# NewPower.net
KiCad netlist of a schematic drawn in Altium Designer
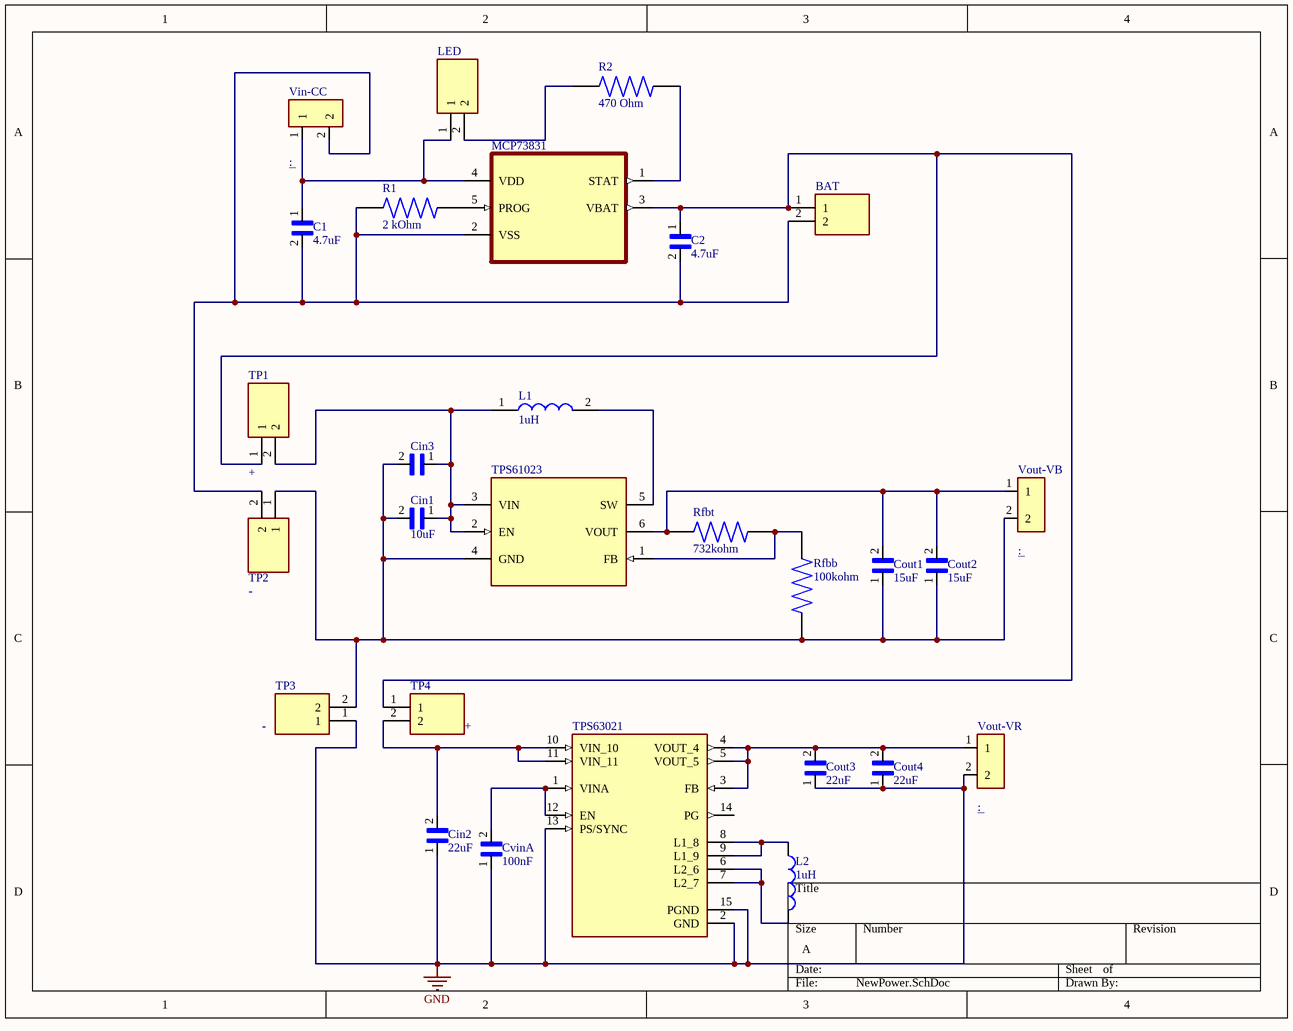
[diagram p0: NewPower.SchDoc]

(export (version "E")
  (design (tool "Eeschema 10.0.6"))
  (components
    (comp (ref "BAT")
      (value "~")
      (footprint "JST_S2B-PH-K-S(LF)(SN)")
      (description "Connector Header Through Hole, Right Angle 2 position")
      (fields (field (name "MP") "S2B-PH-K-S(LF)(SN)") (field (name "MF") "JST Sales America Inc."))
      (libsource (lib "S2B-PH-K-S_LF__SN_") (part "S2B-PH-K-S(LF)(SN)"))
    )
    (comp (ref "C1")
      (value "4.7uF")
      (footprint "CAPC1005X55N")
      (description "4.7ÂµF Â±20% 10V Ceramic Capacitor X5R 0402 (1005 Metric)")
      (fields (field (name "MP") "CL05A475MP5NRNC") (field (name "MF") "Samsung Electro-Mechanics"))
      (libsource (lib "CL05A475MP5NRNC") (part "CL05A475MP5NRNC"))
    )
    (comp (ref "C2")
      (value "4.7uF")
      (footprint "CAPC1005X55N")
      (description "4.7ÂµF Â±20% 10V Ceramic Capacitor X5R 0402 (1005 Metric)")
      (fields (field (name "MP") "CL05A475MP5NRNC") (field (name "MF") "Samsung Electro-Mechanics"))
      (libsource (lib "CL05A475MP5NRNC") (part "CL05A475MP5NRNC"))
    )
    (comp (ref "Cin1")
      (value "10uF")
      (footprint "CAPC2012X88N")
      (description "10渭F 卤 10% Capacitor de cer芒mica 10V X5R 0805 _2012 M茅trico_")
      (fields (field (name "MF") "KEMET") (field (name "DIGI-KEY_PART_NUMBER") "399-4925-1-ND"))
      (libsource (lib "C0805C106K8PACTU") (part "C0805C106K8PACTU"))
    )
    (comp (ref "Cin2")
      (value "22uF")
      (footprint "CAPC1608X100N")
      (description "SMD Capacitor X5R_EIA_ with Capacitance: 22uF Tol. 20%. Rated Voltage: 6.3Vdc")
      (fields (field (name "MF") "Murata") (field (name "DIGI-KEY_PART_NUMBER") "490-7611-1-ND"))
      (libsource (lib "GRM188R60J226MEA0D") (part "GRM188R60J226MEA0D"))
    )
    (comp (ref "Cin3")
      (value "~")
      (footprint "CAPC2012X88N")
      (description "10渭F 卤 10% Capacitor de cer芒mica 10V X5R 0805 _2012 M茅trico_")
      (fields (field (name "MF") "KEMET") (field (name "DIGI-KEY_PART_NUMBER") "399-4925-1-ND"))
      (libsource (lib "C0805C106K8PACTU") (part "C0805C106K8PACTU"))
    )
    (comp (ref "Cout1")
      (value "15uF")
      (footprint "CAPC2012X145N")
      (description "15ÂµF Â±20% 35V Ceramic Capacitor X5R 0805 (2012 Metric)")
      (fields (field (name "MF") "TDK") (field (name "MP") "C2012X5R1V156M125AC"))
      (libsource (lib "C2012X5R1V156M125AC") (part "C2012X5R1V156M125AC"))
    )
    (comp (ref "Cout2")
      (value "15uF")
      (footprint "CAPC2012X145N")
      (description "15ÂµF Â±20% 35V Ceramic Capacitor X5R 0805 (2012 Metric)")
      (fields (field (name "MF") "TDK") (field (name "MP") "C2012X5R1V156M125AC"))
      (libsource (lib "C2012X5R1V156M125AC") (part "C2012X5R1V156M125AC"))
    )
    (comp (ref "Cout3")
      (value "22uF")
      (footprint "CAPC1608X100N")
      (description "SMD Capacitor X5R_EIA_ with Capacitance: 22uF Tol. 20%. Rated Voltage: 6.3Vdc")
      (fields (field (name "MF") "Murata") (field (name "DIGI-KEY_PART_NUMBER") "490-7611-1-ND"))
      (libsource (lib "GRM188R60J226MEA0D") (part "GRM188R60J226MEA0D"))
    )
    (comp (ref "Cout4")
      (value "22uF")
      (footprint "CAPC1608X100N")
      (description "SMD Capacitor X5R_EIA_ with Capacitance: 22uF Tol. 20%. Rated Voltage: 6.3Vdc")
      (fields (field (name "MF") "Murata") (field (name "DIGI-KEY_PART_NUMBER") "490-7611-1-ND"))
      (libsource (lib "GRM188R60J226MEA0D") (part "GRM188R60J226MEA0D"))
    )
    (comp (ref "CvinA")
      (value "100nF")
      (footprint "CAPC1608X90N")
      (description "0.1ÂµF Â±10% 16V Ceramic Capacitor X7R 0603 _1608 Metric_")
      (fields (field (name "MP") "EMK107B7104KA-T") (field (name "MF") "Taiyo Yuden"))
      (libsource (lib "EMK107B7104KA-T") (part "EMK107B7104KA-T"))
    )
    (comp (ref "L1")
      (value "1uH")
      (footprint "SamacSys:74438357010")
      (description "Inductor")
      (fields
        (field (name "MANUFACTURER_PART_NUMBER") "74438357010")
        (field (name "MOUSER PART NUMBER") "710-74438357010")
      )
      (libsource (lib "SamacSys") (part "74438357010"))
    )
    (comp (ref "L2")
      (value "1uH")
      (footprint "INDC2016X100N")
      (description "Inductor with Inductance: 1uH Tol. +/-20%, Package: 0806 (2016)")
      (fields (field (name "DIGI-KEY_PART_NUMBER") "490-18106-2-ND") (field (name "MP") "DFE201610E-1R0M=P2"))
      (libsource (lib "DFE201610E-1R0M_P2") (part "DFE201610E-1R0M=P2"))
    )
    (comp (ref "LED")
      (value "~")
      (footprint "SamacSys:HDRV2W60P0X200_1X2_400X200X525P")
      (description "Connector")
      (fields
        (field (name "MANUFACTURER_PART_NUMBER") "M22-2510205")
        (field (name "MOUSER PART NUMBER") "855-M22-2510205")
      )
      (libsource (lib "SamacSys") (part "M22-2510205"))
    )
    (comp (ref "MCP73831")
      (value "~")
      (footprint "SOT95P280X145-5N")
      (description "Charger IC Lithium Ion/Polymer SOT-23-5")
      (fields (field (name "MF") "Microchip") (field (name "MP") "MCP73831T-2ACI/OT"))
      (libsource (lib "MCP73831T-2ACI_OT") (part "MCP73831T-2ACI/OT"))
    )
    (comp (ref "R1")
      (value "2 kOhm")
      (footprint "RESC3116X65N")
      (fields
        (field (name "MP") "RC1206FR-072KL")
        (field (name "DIGI-KEY_PART_NUMBER") "311-2.00KFRCT-ND")
        (field (name "MF") "Yageo")
      )
      (libsource (lib "RC1206FR-072KL") (part "RC1206FR-072KL"))
    )
    (comp (ref "R2")
      (value "470 Ohm")
      (footprint "RESC3116X65N")
      (description "470 Ohms Â±1% 0.25W, 1/4W Chip Resistor 1206 (3216 Metric) Thick Film")
      (fields (field (name "MP") "RC1206FR-07470RL") (field (name "MF") "Yageo"))
      (libsource (lib "RC1206FR-07470RL") (part "RC1206FR-07470RL"))
    )
    (comp (ref "Rfbb")
      (value "100kohm")
      (footprint "RESC1508X50N")
      (description "100 kOhms Â±1% 0.1W, 1/10W Chip Resistor 0603 (1608 Metric) Automotive AEC-Q200 Thick Film")
      (fields (field (name "MP") "CRCW0603100KFKEA") (field (name "MF") "Vishay"))
      (libsource (lib "CRCW0603100KFKEA") (part "CRCW0603100KFKEA"))
    )
    (comp (ref "Rfbt")
      (value "732kohm")
      (footprint "RESC1508X50N")
      (description "Res Thick Film 0603 732K Ohm 1% 1/10W Â±100ppm/Â°C Molded SMD SMD Paper T/R")
      (fields (field (name "MP") "CRCW0603732KFKEA"))
      (libsource (lib "CRCW0603732KFKEA") (part "CRCW0603732KFKEA"))
    )
    (comp (ref "TP1")
      (value "+")
      (footprint "SamacSys:HDRV2W60P0X200_1X2_400X200X525P")
      (description "Connector")
      (fields
        (field (name "MANUFACTURER_PART_NUMBER") "M22-2510205")
        (field (name "MOUSER PART NUMBER") "855-M22-2510205")
      )
      (libsource (lib "SamacSys") (part "M22-2510205"))
    )
    (comp (ref "TP2")
      (value "-")
      (footprint "SamacSys:HDRV2W60P0X200_1X2_400X200X525P")
      (description "Connector")
      (fields
        (field (name "MANUFACTURER_PART_NUMBER") "M22-2510205")
        (field (name "MOUSER PART NUMBER") "855-M22-2510205")
      )
      (libsource (lib "") (part "M22-2510205_1"))
    )
    (comp (ref "TP3")
      (value "-")
      (footprint "SamacSys:HDRV2W60P0X200_1X2_400X200X525P")
      (description "Connector")
      (fields
        (field (name "MANUFACTURER_PART_NUMBER") "M22-2510205")
        (field (name "MOUSER PART NUMBER") "855-M22-2510205")
      )
      (libsource (lib "") (part "M22-2510205_2"))
    )
    (comp (ref "TP4")
      (value "+")
      (footprint "SamacSys:HDRV2W60P0X200_1X2_400X200X525P")
      (description "Connector")
      (fields
        (field (name "MANUFACTURER_PART_NUMBER") "M22-2510205")
        (field (name "MOUSER PART NUMBER") "855-M22-2510205")
      )
      (libsource (lib "") (part "M22-2510205_3"))
    )
    (comp (ref "TPS61023")
      (value "~")
      (footprint "DRL0006A")
      (description "3-A boost converter with 0.5-V ultra-low input voltage 6-SOT-5X3 -40 to 125")
      (fields (field (name "MP") "TPS61023DRLR") (field (name "MF") "Texas Instruments"))
      (libsource (lib "TPS61023DRLR") (part "TPS61023DRLR"))
    )
    (comp (ref "TPS63021")
      (value "~")
      (footprint "IC_TPS63021DSJR")
      (fields (field (name "MP") "TPS63021DSJR"))
      (libsource (lib "TPS63021DSJR") (part "TPS63021DSJR"))
    )
    (comp (ref "Vin-CC")
      (value "~")
      (footprint "WE_691211720002")
      (description "2 Position Wire to Board Terminal Block 45Â° (135Â°) Angle with Board 0.197 (5.00mm) Through Hole")
      (fields (field (name "MP") "691211720002") (field (name "MF") "Wurth Electronics"))
      (libsource (lib "") (part "691211720002_1"))
    )
    (comp (ref "Vout-VB")
      (value "~")
      (footprint "WE_691211720002")
      (description "2 Position Wire to Board Terminal Block 45Â° (135Â°) Angle with Board 0.197 (5.00mm) Through Hole")
      (fields (field (name "MP") "691211720002") (field (name "MF") "Wurth Electronics"))
      (libsource (lib "691211720002") (part "691211720002"))
    )
    (comp (ref "Vout-VR")
      (value "~")
      (footprint "WE_691211720002")
      (description "2 Position Wire to Board Terminal Block 45Â° (135Â°) Angle with Board 0.197 (5.00mm) Through Hole")
      (fields (field (name "MP") "691211720002") (field (name "MF") "Wurth Electronics"))
      (libsource (lib "691211720002") (part "691211720002"))
    )
  )
  (nets
    (net (code "1") (name "GND") (class "Default")
      (node (ref "Cin2") (pin "1") (pinfunction "1_1") (pintype "passive"))
      (node (ref "Cout3") (pin "1") (pinfunction "1_1") (pintype "passive"))
      (node (ref "Cout4") (pin "1") (pinfunction "1_1") (pintype "passive"))
      (node (ref "CvinA") (pin "1") (pinfunction "1_1") (pintype "passive"))
      (node (ref "TP3") (pin "1") (pinfunction "1_1") (pintype "passive"))
      (node (ref "TPS63021") (pin "13") (pinfunction "PS/SYNC_13") (pintype "input"))
      (node (ref "TPS63021") (pin "15") (pinfunction "PGND_15") (pintype "power_in"))
      (node (ref "TPS63021") (pin "2") (pinfunction "GND_2") (pintype "power_in"))
      (node (ref "Vout-VR") (pin "2") (pinfunction "2_2") (pintype "passive"))
    )
    (net (code "2") (name "Net-(LED-Pad2)") (class "Default")
      (node (ref "LED") (pin "2") (pinfunction "2_2") (pintype "passive"))
      (node (ref "R2") (pin "1") (pinfunction "1_1") (pintype "passive"))
    )
    (net (code "3") (name "Net-(MCP73831-PROG)") (class "Default")
      (node (ref "MCP73831") (pin "5") (pinfunction "PROG_5") (pintype "input"))
      (node (ref "R1") (pin "2") (pinfunction "2_2") (pintype "passive"))
    )
    (net (code "4") (name "Net-(MCP73831-STAT)") (class "Default")
      (node (ref "MCP73831") (pin "1") (pinfunction "STAT_1") (pintype "output"))
      (node (ref "R2") (pin "2") (pinfunction "2_2") (pintype "passive"))
    )
    (net (code "5") (name "Net-(MCP73831-VBAT)") (class "Default")
      (node (ref "BAT") (pin "1") (pinfunction "1_1") (pintype "passive"))
      (node (ref "C2") (pin "1") (pinfunction "1_1") (pintype "passive"))
      (node (ref "MCP73831") (pin "3") (pinfunction "VBAT_3") (pintype "output"))
      (node (ref "TP1") (pin "1") (pinfunction "1_1") (pintype "passive"))
      (node (ref "TP4") (pin "1") (pinfunction "1_1") (pintype "passive"))
    )
    (net (code "6") (name "Net-(MCP73831-VDD)") (class "Default")
      (node (ref "C1") (pin "1") (pinfunction "1_1") (pintype "passive"))
      (node (ref "LED") (pin "1") (pinfunction "1_1") (pintype "passive"))
      (node (ref "MCP73831") (pin "4") (pinfunction "VDD_4") (pintype "power_in"))
      (node (ref "Vin-CC") (pin "1") (pinfunction "1_1") (pintype "passive"))
    )
    (net (code "7") (name "Net-(MCP73831-VSS)") (class "Default")
      (node (ref "BAT") (pin "2") (pinfunction "2_2") (pintype "passive"))
      (node (ref "C1") (pin "2") (pinfunction "2_2") (pintype "passive"))
      (node (ref "C2") (pin "2") (pinfunction "2_2") (pintype "passive"))
      (node (ref "MCP73831") (pin "2") (pinfunction "VSS_2") (pintype "power_in"))
      (node (ref "R1") (pin "1") (pinfunction "1_1") (pintype "passive"))
      (node (ref "TP2") (pin "2") (pinfunction "2_2") (pintype "passive"))
      (node (ref "Vin-CC") (pin "2") (pinfunction "2_2") (pintype "passive"))
    )
    (net (code "8") (name "Net-(TPS61023-EN)") (class "Default")
      (node (ref "Cin1") (pin "1") (pinfunction "1_1") (pintype "passive"))
      (node (ref "Cin3") (pin "1") (pinfunction "1_1") (pintype "passive"))
      (node (ref "L1") (pin "1") (pinfunction "1_1") (pintype "passive"))
      (node (ref "TP1") (pin "2") (pinfunction "2_2") (pintype "passive"))
      (node (ref "TPS61023") (pin "2") (pinfunction "EN_2") (pintype "input"))
      (node (ref "TPS61023") (pin "3") (pinfunction "VIN_3") (pintype "power_in"))
    )
    (net (code "9") (name "Net-(TPS61023-FB)") (class "Default")
      (node (ref "Rfbb") (pin "2") (pinfunction "2_2") (pintype "passive"))
      (node (ref "Rfbt") (pin "2") (pinfunction "2_2") (pintype "passive"))
      (node (ref "TPS61023") (pin "1") (pinfunction "FB_1") (pintype "input"))
    )
    (net (code "10") (name "Net-(TPS61023-GND)") (class "Default")
      (node (ref "Cin1") (pin "2") (pinfunction "2_2") (pintype "passive"))
      (node (ref "Cin3") (pin "2") (pinfunction "2_2") (pintype "passive"))
      (node (ref "Cout1") (pin "1") (pinfunction "1_1") (pintype "passive"))
      (node (ref "Cout2") (pin "1") (pinfunction "1_1") (pintype "passive"))
      (node (ref "Rfbb") (pin "1") (pinfunction "1_1") (pintype "passive"))
      (node (ref "TP2") (pin "1") (pinfunction "1_1") (pintype "passive"))
      (node (ref "TP3") (pin "2") (pinfunction "2_2") (pintype "passive"))
      (node (ref "TPS61023") (pin "4") (pinfunction "GND_4") (pintype "power_in"))
      (node (ref "Vout-VB") (pin "2") (pinfunction "2_2") (pintype "passive"))
    )
    (net (code "11") (name "Net-(TPS61023-SW)") (class "Default")
      (node (ref "L1") (pin "2") (pinfunction "2_2") (pintype "passive"))
      (node (ref "TPS61023") (pin "5") (pinfunction "SW_5") (pintype "power_in"))
    )
    (net (code "12") (name "Net-(TPS61023-VOUT)") (class "Default")
      (node (ref "Cout1") (pin "2") (pinfunction "2_2") (pintype "passive"))
      (node (ref "Cout2") (pin "2") (pinfunction "2_2") (pintype "passive"))
      (node (ref "Rfbt") (pin "1") (pinfunction "1_1") (pintype "passive"))
      (node (ref "TPS61023") (pin "6") (pinfunction "VOUT_6") (pintype "power_in"))
      (node (ref "Vout-VB") (pin "1") (pinfunction "1_1") (pintype "passive"))
    )
    (net (code "13") (name "Net-(TPS63021-EN)") (class "Default")
      (node (ref "CvinA") (pin "2") (pinfunction "2_2") (pintype "passive"))
      (node (ref "TPS63021") (pin "1") (pinfunction "VINA_1") (pintype "input"))
      (node (ref "TPS63021") (pin "12") (pinfunction "EN_12") (pintype "input"))
    )
    (net (code "14") (name "Net-(TPS63021-FB)") (class "Default")
      (node (ref "Cout3") (pin "2") (pinfunction "2_2") (pintype "passive"))
      (node (ref "Cout4") (pin "2") (pinfunction "2_2") (pintype "passive"))
      (node (ref "TPS63021") (pin "3") (pinfunction "FB_3") (pintype "input"))
      (node (ref "TPS63021") (pin "4") (pinfunction "VOUT_4_4") (pintype "output"))
      (node (ref "TPS63021") (pin "5") (pinfunction "VOUT_5_5") (pintype "output"))
      (node (ref "Vout-VR") (pin "1") (pinfunction "1_1") (pintype "passive"))
    )
    (net (code "15") (name "Net-(TPS63021-L1_8)") (class "Default")
      (node (ref "L2") (pin "1") (pinfunction "1_1") (pintype "passive"))
      (node (ref "TPS63021") (pin "8") (pinfunction "L1_8_8") (pintype "passive"))
      (node (ref "TPS63021") (pin "9") (pinfunction "L1_9_9") (pintype "passive"))
    )
    (net (code "16") (name "Net-(TPS63021-L2_6)") (class "Default")
      (node (ref "L2") (pin "2") (pinfunction "2_2") (pintype "passive"))
      (node (ref "TPS63021") (pin "6") (pinfunction "L2_6_6") (pintype "passive"))
      (node (ref "TPS63021") (pin "7") (pinfunction "L2_7_7") (pintype "passive"))
    )
    (net (code "17") (name "Net-(TPS63021-VIN_10)") (class "Default")
      (node (ref "Cin2") (pin "2") (pinfunction "2_2") (pintype "passive"))
      (node (ref "TP4") (pin "2") (pinfunction "2_2") (pintype "passive"))
      (node (ref "TPS63021") (pin "10") (pinfunction "VIN_10_10") (pintype "input"))
      (node (ref "TPS63021") (pin "11") (pinfunction "VIN_11_11") (pintype "input"))
    )
    (net (code "18") (name "unconnected-(TPS63021-PG-Pad14)") (class "Default")
      (node (ref "TPS63021") (pin "14") (pinfunction "PG_14") (pintype "output"))
    )
  )
)
